# FrontDoorConnecteur.net
KiCad netlist of a schematic drawn in Altium Designer
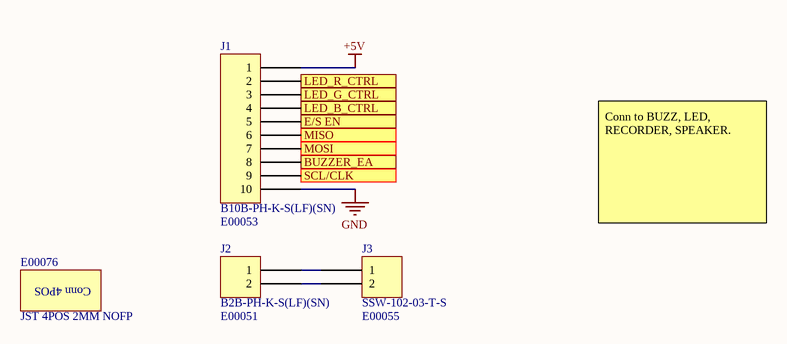
[diagram p0: FrontDoorConnecteur.SchDoc]

(export (version "E")
  (design (tool "Eeschema 10.0.6"))
  (components
    (comp (ref "H1")
      (value "JST 4POS 2MM NOFP")
      (description "No footprint, for BOM")
      (fields (field (name "ADAM INVENTORY NUMBER 1") "E00076"))
      (libsource (lib "ADAM LIBRARY") (part "CONN JST 4POS 2MM NOFP"))
    )
    (comp (ref "J1")
      (value "B10B-PH-K-S(LF)(SN)")
      (footprint "CONN JST 10PIN")
      (description "CONN HEADER VERT 10POS 2MM")
      (fields
        (field (name "MANUFACTURER") "JST Sales America Inc.")
        (field (name "ADAM INVENTORY NUMBER 1") "E00053")
      )
      (libsource (lib "ADAM LIBRARY") (part "CONN JST 10POS TH"))
    )
    (comp (ref "J2")
      (value "B2B-PH-K-S(LF)(SN)")
      (footprint "CONN JST 2PIN")
      (description "CONN HEADER VERT 2POS 2MM")
      (fields
        (field (name "MANUFACTURER") "JST Sales America Inc.")
        (field (name "ADAM INVENTORY NUMBER 1") "E00051")
      )
      (libsource (lib "ADAM LIBRARY") (part "CONN JST 2PIN TH"))
    )
    (comp (ref "J3")
      (value "SSW-102-03-T-S")
      (footprint "CONN FEM HEADER 2PIN")
      (description "CONN RCPT 2POS 0.1 TIN")
      (fields (field (name "MANUFACTURER") "Samtec Inc.") (field (name "ADAM INVENTORY NUMBER 1") "E00055"))
      (libsource (lib "ADAM LIBRARY") (part "CONN FEM HEADER 2POS"))
    )
  )
  (nets
    (net (code "1") (name "+5V") (class "Default")
      (node (ref "J1") (pin "1") (pinfunction "1_1") (pintype "passive"))
    )
    (net (code "2") (name "/BUZZER_EA") (class "Default")
      (node (ref "J1") (pin "8") (pinfunction "8_8") (pintype "passive"))
    )
    (net (code "3") (name "/E{slash}S EN") (class "Default")
      (node (ref "J1") (pin "5") (pinfunction "5_5") (pintype "passive"))
    )
    (net (code "4") (name "/LED_B_CTRL") (class "Default")
      (node (ref "J1") (pin "4") (pinfunction "4_4") (pintype "passive"))
    )
    (net (code "5") (name "/LED_G_CTRL") (class "Default")
      (node (ref "J1") (pin "3") (pinfunction "3_3") (pintype "passive"))
    )
    (net (code "6") (name "/LED_R_CTRL") (class "Default")
      (node (ref "J1") (pin "2") (pinfunction "2_2") (pintype "passive"))
    )
    (net (code "7") (name "/MISO") (class "Default")
      (node (ref "J1") (pin "6") (pinfunction "6_6") (pintype "passive"))
    )
    (net (code "8") (name "/MOSI") (class "Default")
      (node (ref "J1") (pin "7") (pinfunction "7_7") (pintype "passive"))
    )
    (net (code "9") (name "/SCL{slash}CLK") (class "Default")
      (node (ref "J1") (pin "9") (pinfunction "9_9") (pintype "passive"))
    )
    (net (code "10") (name "GND") (class "Default")
      (node (ref "J1") (pin "10") (pinfunction "10_10") (pintype "passive"))
    )
    (net (code "11") (name "Net-(J2-Pad1)") (class "Default")
      (node (ref "J2") (pin "1") (pinfunction "1_1") (pintype "passive"))
      (node (ref "J3") (pin "1") (pinfunction "1_1") (pintype "passive"))
    )
    (net (code "12") (name "Net-(J2-Pad2)") (class "Default")
      (node (ref "J2") (pin "2") (pinfunction "2_2") (pintype "passive"))
      (node (ref "J3") (pin "2") (pinfunction "2_2") (pintype "passive"))
    )
  )
)
